# POWER.net
KiCad netlist of a schematic drawn in Altium Designer
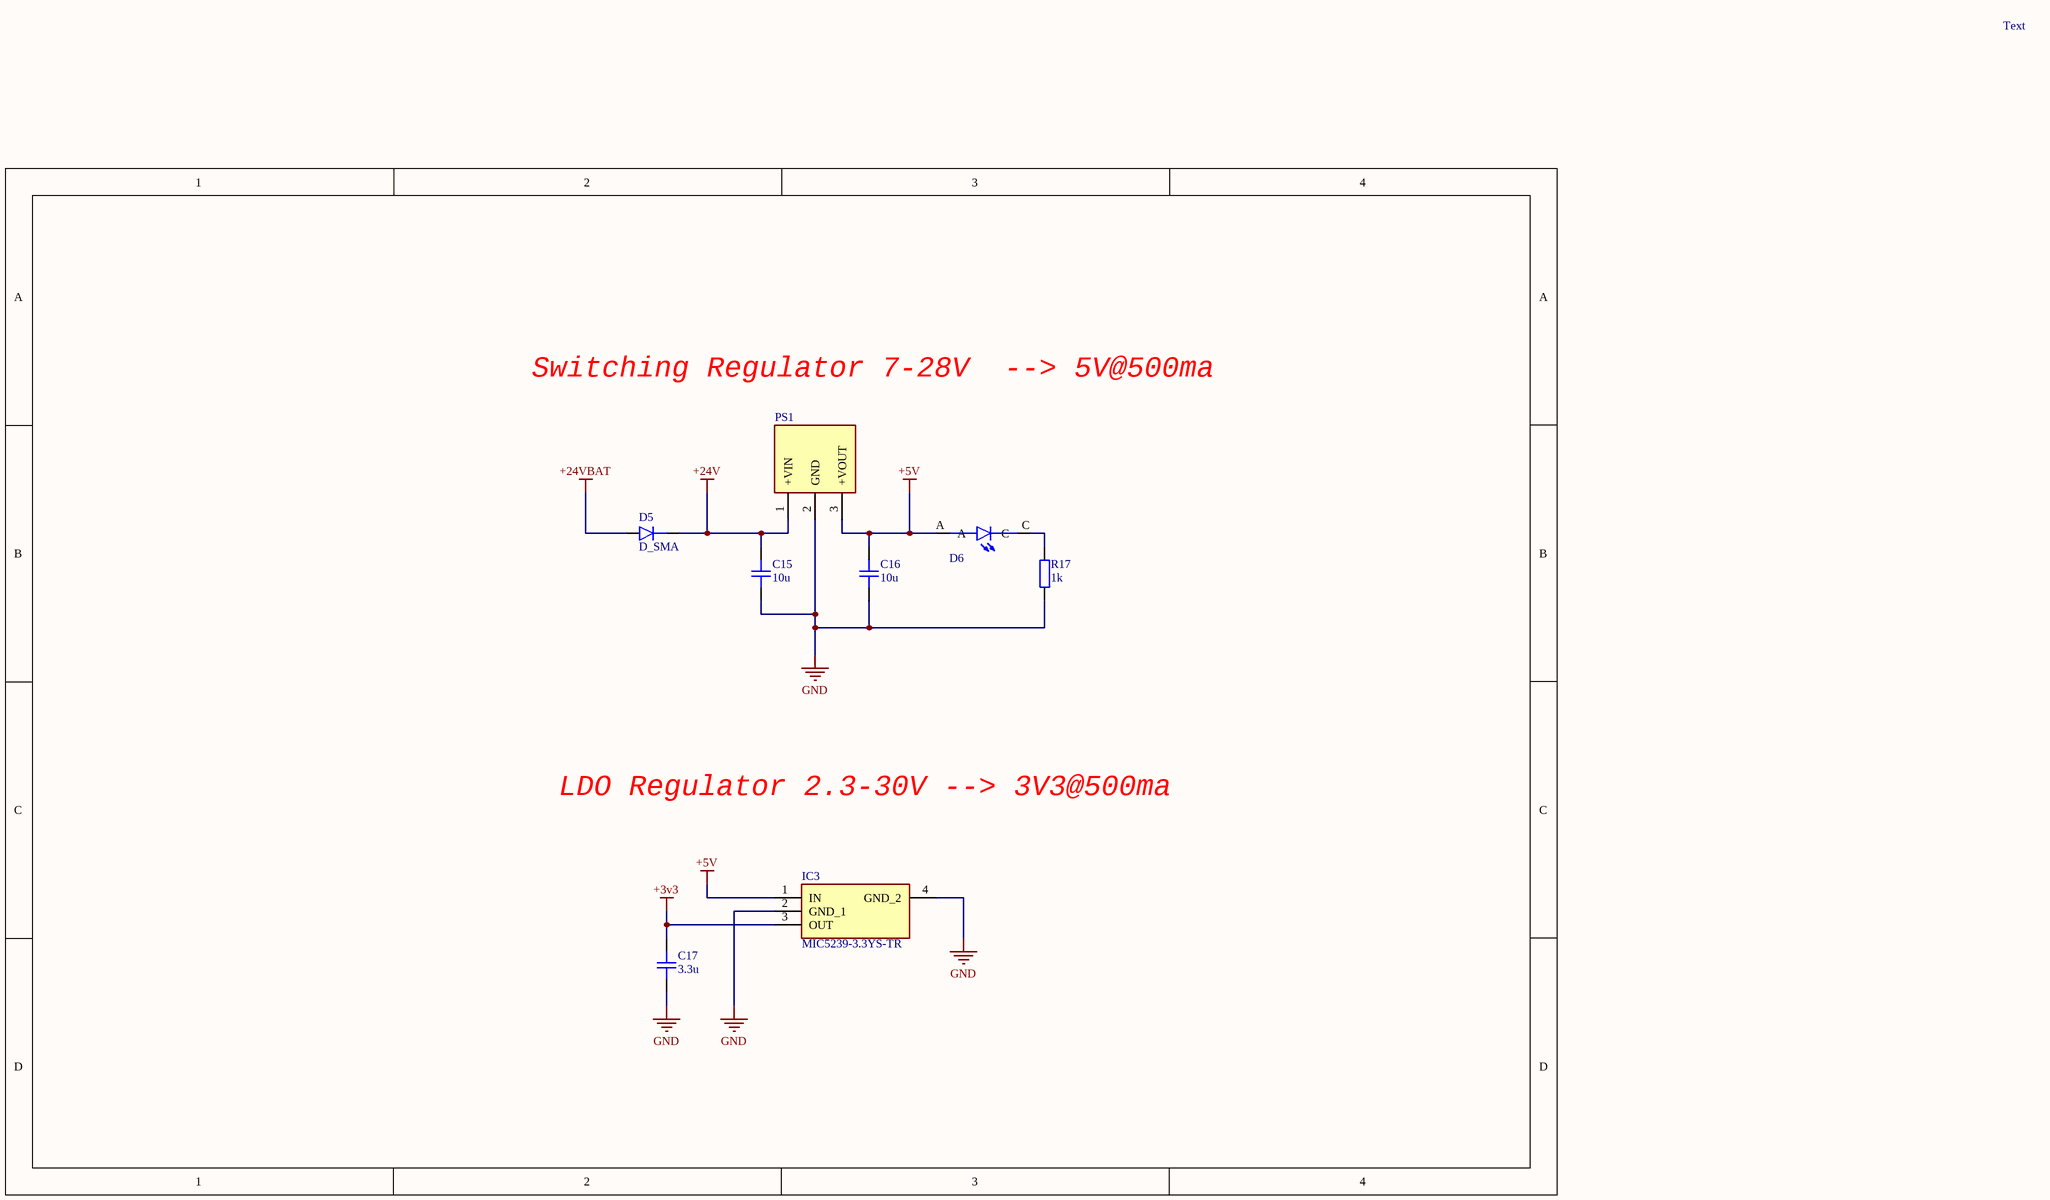
[diagram p0: POWER.SchDoc]

(export (version "E")
  (design (tool "Eeschema 10.0.6"))
  (components
    (comp (ref "C15")
      (value "10u")
      (footprint "CAP_0805")
      (description "Capacitor SMD 0805 10V")
      (libsource (lib "Schematic-Lib-PhilsLab") (part "CAP_0805_10V"))
    )
    (comp (ref "C16")
      (value "10u")
      (footprint "CAP_0805")
      (description "Capacitor SMD 0805 10V")
      (libsource (lib "Schematic-Lib-PhilsLab") (part "CAP_0805_10V"))
    )
    (comp (ref "C17")
      (value "3.3u")
      (footprint "CAP_0805")
      (description "Capacitor SMD 0805 10V")
      (libsource (lib "Schematic-Lib-PhilsLab") (part "CAP_0805_10V"))
    )
    (comp (ref "D5")
      (value "D_SMA")
      (footprint "DO-214AC-2 (SMA)")
      (description "Diode SMD SMA (DO-214AA)")
      (libsource (lib "Schematic-Lib-PhilsLab") (part "D_SMA"))
    )
    (comp (ref "D6")
      (value "SML-LXT0805IW-TR")
      (footprint "LEDC2012X120N")
      (description "Red - LED Indication - Discrete 2V 0805 (2012 Metric)")
      (fields (field (name "MF") "Lumex Opto/Components"))
      (libsource (lib "SML-LXT0805IW-TR") (part "SML-LXT0805IW-TR"))
    )
    (comp (ref "IC3")
      (value "MIC5239-3.3YS-TR")
      (footprint "Pedro_pcb_lib:SOT230P700X180-4N")
      (description "Integrated Circuit")
      (fields (field (name "MOUSER PART NUMBER") "998-MIC5239-3.3YSTR"))
      (libsource (lib "*") (part "MIC5239-3.3YS-TR"))
    )
    (comp (ref "PS1")
      (value "R-78E5.0-0.5")
      (footprint "R78E5005")
      (description "Power Supply")
      (fields (field (name "MOUSER PART NUMBER") "919-R-78E5.0-0.5"))
      (libsource (lib "Pedro_Integrated_Library") (part "R-78E5.0-0.5"))
    )
    (comp (ref "R17")
      (value "1k")
      (footprint "RES_0805")
      (description "Resistor SMD 0805")
      (libsource (lib "Schematic-Lib-PhilsLab") (part "RES_0805"))
    )
  )
  (nets
    (net (code "1") (name "+3v3") (class "Default")
      (node (ref "C17") (pin "2") (pinfunction "2_2") (pintype "passive"))
      (node (ref "IC3") (pin "3") (pinfunction "OUT_3") (pintype "passive"))
    )
    (net (code "2") (name "+5V") (class "Default")
      (node (ref "C16") (pin "2") (pinfunction "2_2") (pintype "passive"))
      (node (ref "D6") (pin "A") (pinfunction "A_A") (pintype "passive"))
      (node (ref "IC3") (pin "1") (pinfunction "IN_1") (pintype "passive"))
      (node (ref "PS1") (pin "3") (pinfunction "+VOUT_3") (pintype "passive"))
    )
    (net (code "3") (name "+24V") (class "Default")
      (node (ref "C15") (pin "2") (pinfunction "2_2") (pintype "passive"))
      (node (ref "D5") (pin "K") (pinfunction "K_K") (pintype "passive"))
      (node (ref "PS1") (pin "1") (pinfunction "+VIN_1") (pintype "passive"))
    )
    (net (code "4") (name "+24VBAT") (class "Default")
      (node (ref "D5") (pin "A") (pinfunction "A_A") (pintype "passive"))
    )
    (net (code "5") (name "GND") (class "Default")
      (node (ref "C15") (pin "1") (pinfunction "1_1") (pintype "passive"))
      (node (ref "C16") (pin "1") (pinfunction "1_1") (pintype "passive"))
      (node (ref "C17") (pin "1") (pinfunction "1_1") (pintype "passive"))
      (node (ref "IC3") (pin "2") (pinfunction "GND_1_2") (pintype "passive"))
      (node (ref "IC3") (pin "4") (pinfunction "GND_2_4") (pintype "passive"))
      (node (ref "PS1") (pin "2") (pinfunction "GND_2") (pintype "passive"))
      (node (ref "R17") (pin "2") (pinfunction "2_2") (pintype "passive"))
    )
    (net (code "6") (name "Net-(D6-PadC)") (class "Default")
      (node (ref "D6") (pin "C") (pinfunction "C_C") (pintype "passive"))
      (node (ref "R17") (pin "1") (pinfunction "1_1") (pintype "passive"))
    )
  )
)
